# Power.net
KiCad netlist of a schematic drawn in Altium Designer
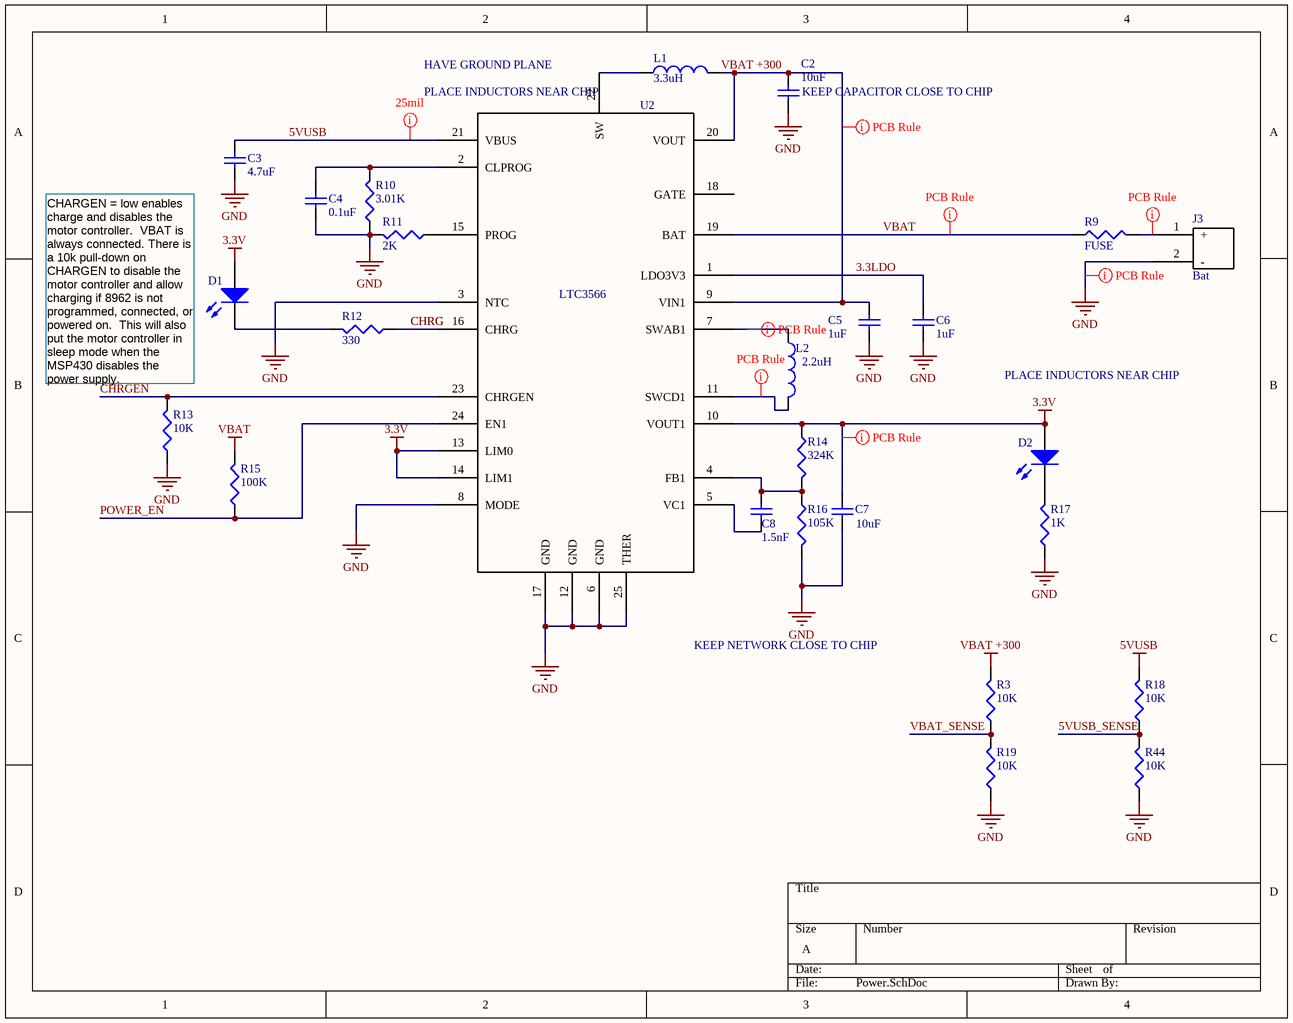
[diagram p0: Power.SchDoc]

(export (version "E")
  (design (tool "Eeschema 10.0.6"))
  (components
    (comp (ref "C2")
      (value "10uF")
      (footprint "CAPC1608L")
      (description "Capacitor")
      (fields (field (name "Comment") "Cap") (field (name "PUBLISHER") "Altium Limited"))
      (libsource (lib "Miscellaneous Devices") (part "Cap"))
    )
    (comp (ref "C3")
      (value "4.7uF")
      (footprint "CAPC1608L")
      (description "Capacitor")
      (fields (field (name "Comment") "Cap") (field (name "PUBLISHER") "Altium Limited"))
      (libsource (lib "Miscellaneous Devices") (part "Cap"))
    )
    (comp (ref "C4")
      (value "0.1uF")
      (footprint "CAPC1005L")
      (description "Capacitor")
      (fields (field (name "Comment") "Cap") (field (name "PUBLISHER") "Altium Limited"))
      (libsource (lib "Miscellaneous Devices") (part "Cap"))
    )
    (comp (ref "C5")
      (value "1uF")
      (footprint "CAPC1608L")
      (description "Capacitor")
      (fields (field (name "Comment") "Cap") (field (name "PUBLISHER") "Altium Limited"))
      (libsource (lib "Miscellaneous Devices") (part "Cap"))
    )
    (comp (ref "C6")
      (value "1uF")
      (footprint "CAPC1608L")
      (description "Capacitor")
      (fields (field (name "Comment") "Cap") (field (name "PUBLISHER") "Altium Limited"))
      (libsource (lib "Miscellaneous Devices") (part "Cap"))
    )
    (comp (ref "C7")
      (value "10uF")
      (footprint "CAPC1608L")
      (description "Capacitor")
      (fields (field (name "Comment") "Cap") (field (name "PUBLISHER") "Altium Limited"))
      (libsource (lib "Miscellaneous Devices") (part "Cap"))
    )
    (comp (ref "C8")
      (value "1.5nF")
      (footprint "CAPC1005L")
      (description "Capacitor")
      (fields (field (name "Comment") "Cap") (field (name "PUBLISHER") "Altium Limited"))
      (libsource (lib "Miscellaneous Devices") (part "Cap"))
    )
    (comp (ref "D1")
      (value "Charge")
      (footprint "INDC2012L")
      (description "Typical RED, GREEN, YELLOW, AMBER GaAs LED")
      (fields (field (name "PUBLISHER") "Altium Limited"))
      (libsource (lib "Miscellaneous Devices") (part "LED2"))
    )
    (comp (ref "D2")
      (value "Power")
      (footprint "INDC2012L")
      (description "Typical RED, GREEN, YELLOW, AMBER GaAs LED")
      (fields (field (name "PUBLISHER") "Altium Limited"))
      (libsource (lib "Miscellaneous Devices") (part "LED2"))
    )
    (comp (ref "J3")
      (value "Bat")
      (footprint "BatteryConnJST")
      (libsource (lib "mrone") (part "BatteryConnJST"))
    )
    (comp (ref "L1") (value "3.3uH") (footprint "IndPow") (libsource (lib "mrone") (part "Inductor")))
    (comp (ref "L2") (value "2.2uH") (footprint "IndPow") (libsource (lib "mrone") (part "Inductor")))
    (comp (ref "R3")
      (value "10K")
      (footprint "RESC1608L")
      (description "Resistor")
      (fields (field (name "Comment") "Res3") (field (name "PUBLISHER") "Altium Limited"))
      (libsource (lib "Miscellaneous Devices") (part "Res3"))
    )
    (comp (ref "R9")
      (value "FUSE")
      (footprint "RESC3225L")
      (description "Resistor")
      (fields (field (name "Comment") "Res3") (field (name "PUBLISHER") "Altium Limited"))
      (libsource (lib "Miscellaneous Devices") (part "Res3"))
    )
    (comp (ref "R10")
      (value "3.01K")
      (footprint "RESC1608L")
      (description "Resistor")
      (fields (field (name "Comment") "Res3") (field (name "PUBLISHER") "Altium Limited"))
      (libsource (lib "Miscellaneous Devices") (part "Res3"))
    )
    (comp (ref "R11")
      (value "2K")
      (footprint "RESC1608L")
      (description "Resistor")
      (fields (field (name "Comment") "Res3") (field (name "PUBLISHER") "Altium Limited"))
      (libsource (lib "Miscellaneous Devices") (part "Res3"))
    )
    (comp (ref "R12")
      (value "330")
      (footprint "RESC1608L")
      (description "Resistor")
      (fields (field (name "Comment") "Res3") (field (name "PUBLISHER") "Altium Limited"))
      (libsource (lib "Miscellaneous Devices") (part "Res3"))
    )
    (comp (ref "R13")
      (value "10K")
      (footprint "RESC1608L")
      (description "Resistor")
      (fields (field (name "Comment") "Res3") (field (name "PUBLISHER") "Altium Limited"))
      (libsource (lib "Miscellaneous Devices") (part "Res3"))
    )
    (comp (ref "R14")
      (value "324K")
      (footprint "RESC1608L")
      (description "Resistor")
      (fields (field (name "Comment") "Res3") (field (name "PUBLISHER") "Altium Limited"))
      (libsource (lib "Miscellaneous Devices") (part "Res3"))
    )
    (comp (ref "R15")
      (value "100K")
      (footprint "RESC1608L")
      (description "Resistor")
      (fields (field (name "Comment") "Res3") (field (name "PUBLISHER") "Altium Limited"))
      (libsource (lib "Miscellaneous Devices") (part "Res3"))
    )
    (comp (ref "R16")
      (value "105K")
      (footprint "RESC1608L")
      (description "Resistor")
      (fields (field (name "Comment") "Res3") (field (name "PUBLISHER") "Altium Limited"))
      (libsource (lib "Miscellaneous Devices") (part "Res3"))
    )
    (comp (ref "R17")
      (value "1K")
      (footprint "RESC1608L")
      (description "Resistor")
      (fields (field (name "Comment") "Res3") (field (name "PUBLISHER") "Altium Limited"))
      (libsource (lib "Miscellaneous Devices") (part "Res3"))
    )
    (comp (ref "R18")
      (value "10K")
      (footprint "RESC1608L")
      (description "Resistor")
      (fields (field (name "Comment") "Res3") (field (name "PUBLISHER") "Altium Limited"))
      (libsource (lib "Miscellaneous Devices") (part "Res3"))
    )
    (comp (ref "R19")
      (value "10K")
      (footprint "RESC1608L")
      (description "Resistor")
      (fields (field (name "Comment") "Res3") (field (name "PUBLISHER") "Altium Limited"))
      (libsource (lib "Miscellaneous Devices") (part "Res3"))
    )
    (comp (ref "R44")
      (value "10K")
      (footprint "RESC1608L")
      (description "Resistor")
      (fields (field (name "Comment") "Res3") (field (name "PUBLISHER") "Altium Limited"))
      (libsource (lib "Miscellaneous Devices") (part "Res3"))
    )
    (comp (ref "U2")
      (value "LTC3566")
      (footprint "QFN-24")
      (libsource (lib "Schematic Components") (part "LTC3566"))
    )
  )
  (nets
    (net (code "1") (name "/3.3LDO") (class "Default")
      (node (ref "C6") (pin "1") (pinfunction "1_1") (pintype "passive"))
      (node (ref "U2") (pin "1") (pinfunction "LDO3V3_1") (pintype "passive"))
    )
    (net (code "2") (name "/5VUSB_SENSE") (class "Default")
      (node (ref "R18") (pin "1") (pinfunction "1_1") (pintype "passive"))
      (node (ref "R44") (pin "2") (pinfunction "2_2") (pintype "passive"))
    )
    (net (code "3") (name "/CHRG") (class "Default")
      (node (ref "R12") (pin "1") (pinfunction "1_1") (pintype "passive"))
      (node (ref "U2") (pin "16") (pinfunction "CHRG_16") (pintype "passive"))
    )
    (net (code "4") (name "/CHRGEN") (class "Default")
      (node (ref "R13") (pin "2") (pinfunction "2_2") (pintype "passive"))
      (node (ref "U2") (pin "23") (pinfunction "CHRGEN_23") (pintype "passive"))
    )
    (net (code "5") (name "/POWER_EN") (class "Default")
      (node (ref "R15") (pin "1") (pinfunction "1_1") (pintype "passive"))
      (node (ref "U2") (pin "24") (pinfunction "EN1_24") (pintype "passive"))
    )
    (net (code "6") (name "/VBAT_SENSE") (class "Default")
      (node (ref "R19") (pin "2") (pinfunction "2_2") (pintype "passive"))
      (node (ref "R3") (pin "1") (pinfunction "1_1") (pintype "passive"))
    )
    (net (code "7") (name "3.3V") (class "Default")
      (node (ref "C7") (pin "2") (pinfunction "2_2") (pintype "passive"))
      (node (ref "D1") (pin "1") (pinfunction "A_1") (pintype "passive"))
      (node (ref "D2") (pin "1") (pinfunction "A_1") (pintype "passive"))
      (node (ref "R14") (pin "1") (pinfunction "1_1") (pintype "passive"))
      (node (ref "U2") (pin "10") (pinfunction "VOUT1_10") (pintype "passive"))
      (node (ref "U2") (pin "13") (pinfunction "LIM0_13") (pintype "passive"))
      (node (ref "U2") (pin "14") (pinfunction "LIM1_14") (pintype "passive"))
    )
    (net (code "8") (name "5VUSB") (class "Default")
      (node (ref "C3") (pin "2") (pinfunction "2_2") (pintype "passive"))
      (node (ref "R18") (pin "2") (pinfunction "2_2") (pintype "passive"))
      (node (ref "U2") (pin "21") (pinfunction "VBUS_21") (pintype "passive"))
    )
    (net (code "9") (name "GND") (class "Default")
      (node (ref "C2") (pin "1") (pinfunction "1_1") (pintype "passive"))
      (node (ref "C3") (pin "1") (pinfunction "1_1") (pintype "passive"))
      (node (ref "C4") (pin "1") (pinfunction "1_1") (pintype "passive"))
      (node (ref "C5") (pin "2") (pinfunction "2_2") (pintype "passive"))
      (node (ref "C6") (pin "2") (pinfunction "2_2") (pintype "passive"))
      (node (ref "C7") (pin "1") (pinfunction "1_1") (pintype "passive"))
      (node (ref "J3") (pin "2") (pinfunction "-_2") (pintype "passive"))
      (node (ref "R10") (pin "1") (pinfunction "1_1") (pintype "passive"))
      (node (ref "R11") (pin "2") (pinfunction "2_2") (pintype "passive"))
      (node (ref "R13") (pin "1") (pinfunction "1_1") (pintype "passive"))
      (node (ref "R16") (pin "2") (pinfunction "2_2") (pintype "passive"))
      (node (ref "R17") (pin "1") (pinfunction "1_1") (pintype "passive"))
      (node (ref "R19") (pin "1") (pinfunction "1_1") (pintype "passive"))
      (node (ref "R44") (pin "1") (pinfunction "1_1") (pintype "passive"))
      (node (ref "U2") (pin "12") (pinfunction "GND_12") (pintype "passive"))
      (node (ref "U2") (pin "17") (pinfunction "GND_17") (pintype "passive"))
      (node (ref "U2") (pin "25") (pinfunction "THER_25") (pintype "passive"))
      (node (ref "U2") (pin "3") (pinfunction "NTC_3") (pintype "passive"))
      (node (ref "U2") (pin "6") (pinfunction "GND_6") (pintype "passive"))
      (node (ref "U2") (pin "8") (pinfunction "MODE_8") (pintype "passive"))
    )
    (net (code "10") (name "Net-(D1-K)") (class "Default")
      (node (ref "D1") (pin "2") (pinfunction "K_2") (pintype "passive"))
      (node (ref "R12") (pin "2") (pinfunction "2_2") (pintype "passive"))
    )
    (net (code "11") (name "Net-(D2-K)") (class "Default")
      (node (ref "D2") (pin "2") (pinfunction "K_2") (pintype "passive"))
      (node (ref "R17") (pin "2") (pinfunction "2_2") (pintype "passive"))
    )
    (net (code "12") (name "Net-(J3-+)") (class "Default")
      (node (ref "J3") (pin "1") (pinfunction "+_1") (pintype "passive"))
      (node (ref "R9") (pin "2") (pinfunction "2_2") (pintype "passive"))
    )
    (net (code "13") (name "Net-(U2-CLPROG)") (class "Default")
      (node (ref "C4") (pin "2") (pinfunction "2_2") (pintype "passive"))
      (node (ref "R10") (pin "2") (pinfunction "2_2") (pintype "passive"))
      (node (ref "U2") (pin "2") (pinfunction "CLPROG_2") (pintype "passive"))
    )
    (net (code "14") (name "Net-(U2-FB1)") (class "Default")
      (node (ref "C8") (pin "1") (pinfunction "1_1") (pintype "passive"))
      (node (ref "R14") (pin "2") (pinfunction "2_2") (pintype "passive"))
      (node (ref "R16") (pin "1") (pinfunction "1_1") (pintype "passive"))
      (node (ref "U2") (pin "4") (pinfunction "FB1_4") (pintype "passive"))
    )
    (net (code "15") (name "Net-(U2-PROG)") (class "Default")
      (node (ref "R11") (pin "1") (pinfunction "1_1") (pintype "passive"))
      (node (ref "U2") (pin "15") (pinfunction "PROG_15") (pintype "passive"))
    )
    (net (code "16") (name "Net-(U2-SW)") (class "Default")
      (node (ref "L1") (pin "1") (pinfunction "1_1") (pintype "passive"))
      (node (ref "U2") (pin "22") (pinfunction "SW_22") (pintype "passive"))
    )
    (net (code "17") (name "Net-(U2-SWAB1)") (class "Default")
      (node (ref "L2") (pin "1") (pinfunction "1_1") (pintype "passive"))
      (node (ref "U2") (pin "7") (pinfunction "SWAB1_7") (pintype "passive"))
    )
    (net (code "18") (name "Net-(U2-SWCD1)") (class "Default")
      (node (ref "L2") (pin "2") (pinfunction "2_2") (pintype "passive"))
      (node (ref "U2") (pin "11") (pinfunction "SWCD1_11") (pintype "passive"))
    )
    (net (code "19") (name "Net-(U2-VC1)") (class "Default")
      (node (ref "C8") (pin "2") (pinfunction "2_2") (pintype "passive"))
      (node (ref "U2") (pin "5") (pinfunction "VC1_5") (pintype "passive"))
    )
    (net (code "20") (name "VBAT") (class "Default")
      (node (ref "R15") (pin "2") (pinfunction "2_2") (pintype "passive"))
      (node (ref "R9") (pin "1") (pinfunction "1_1") (pintype "passive"))
      (node (ref "U2") (pin "19") (pinfunction "BAT_19") (pintype "passive"))
    )
    (net (code "21") (name "VBAT +300") (class "Default")
      (node (ref "C2") (pin "2") (pinfunction "2_2") (pintype "passive"))
      (node (ref "C5") (pin "1") (pinfunction "1_1") (pintype "passive"))
      (node (ref "L1") (pin "2") (pinfunction "2_2") (pintype "passive"))
      (node (ref "R3") (pin "2") (pinfunction "2_2") (pintype "passive"))
      (node (ref "U2") (pin "20") (pinfunction "VOUT_20") (pintype "passive"))
      (node (ref "U2") (pin "9") (pinfunction "VIN1_9") (pintype "passive"))
    )
    (net (code "22") (name "unconnected-(U2-GATE-Pad18)") (class "Default")
      (node (ref "U2") (pin "18") (pinfunction "GATE_18") (pintype "passive"))
    )
  )
)
